# IV_FET_Array_v2.net
KiCad netlist of a schematic drawn in EAGLE
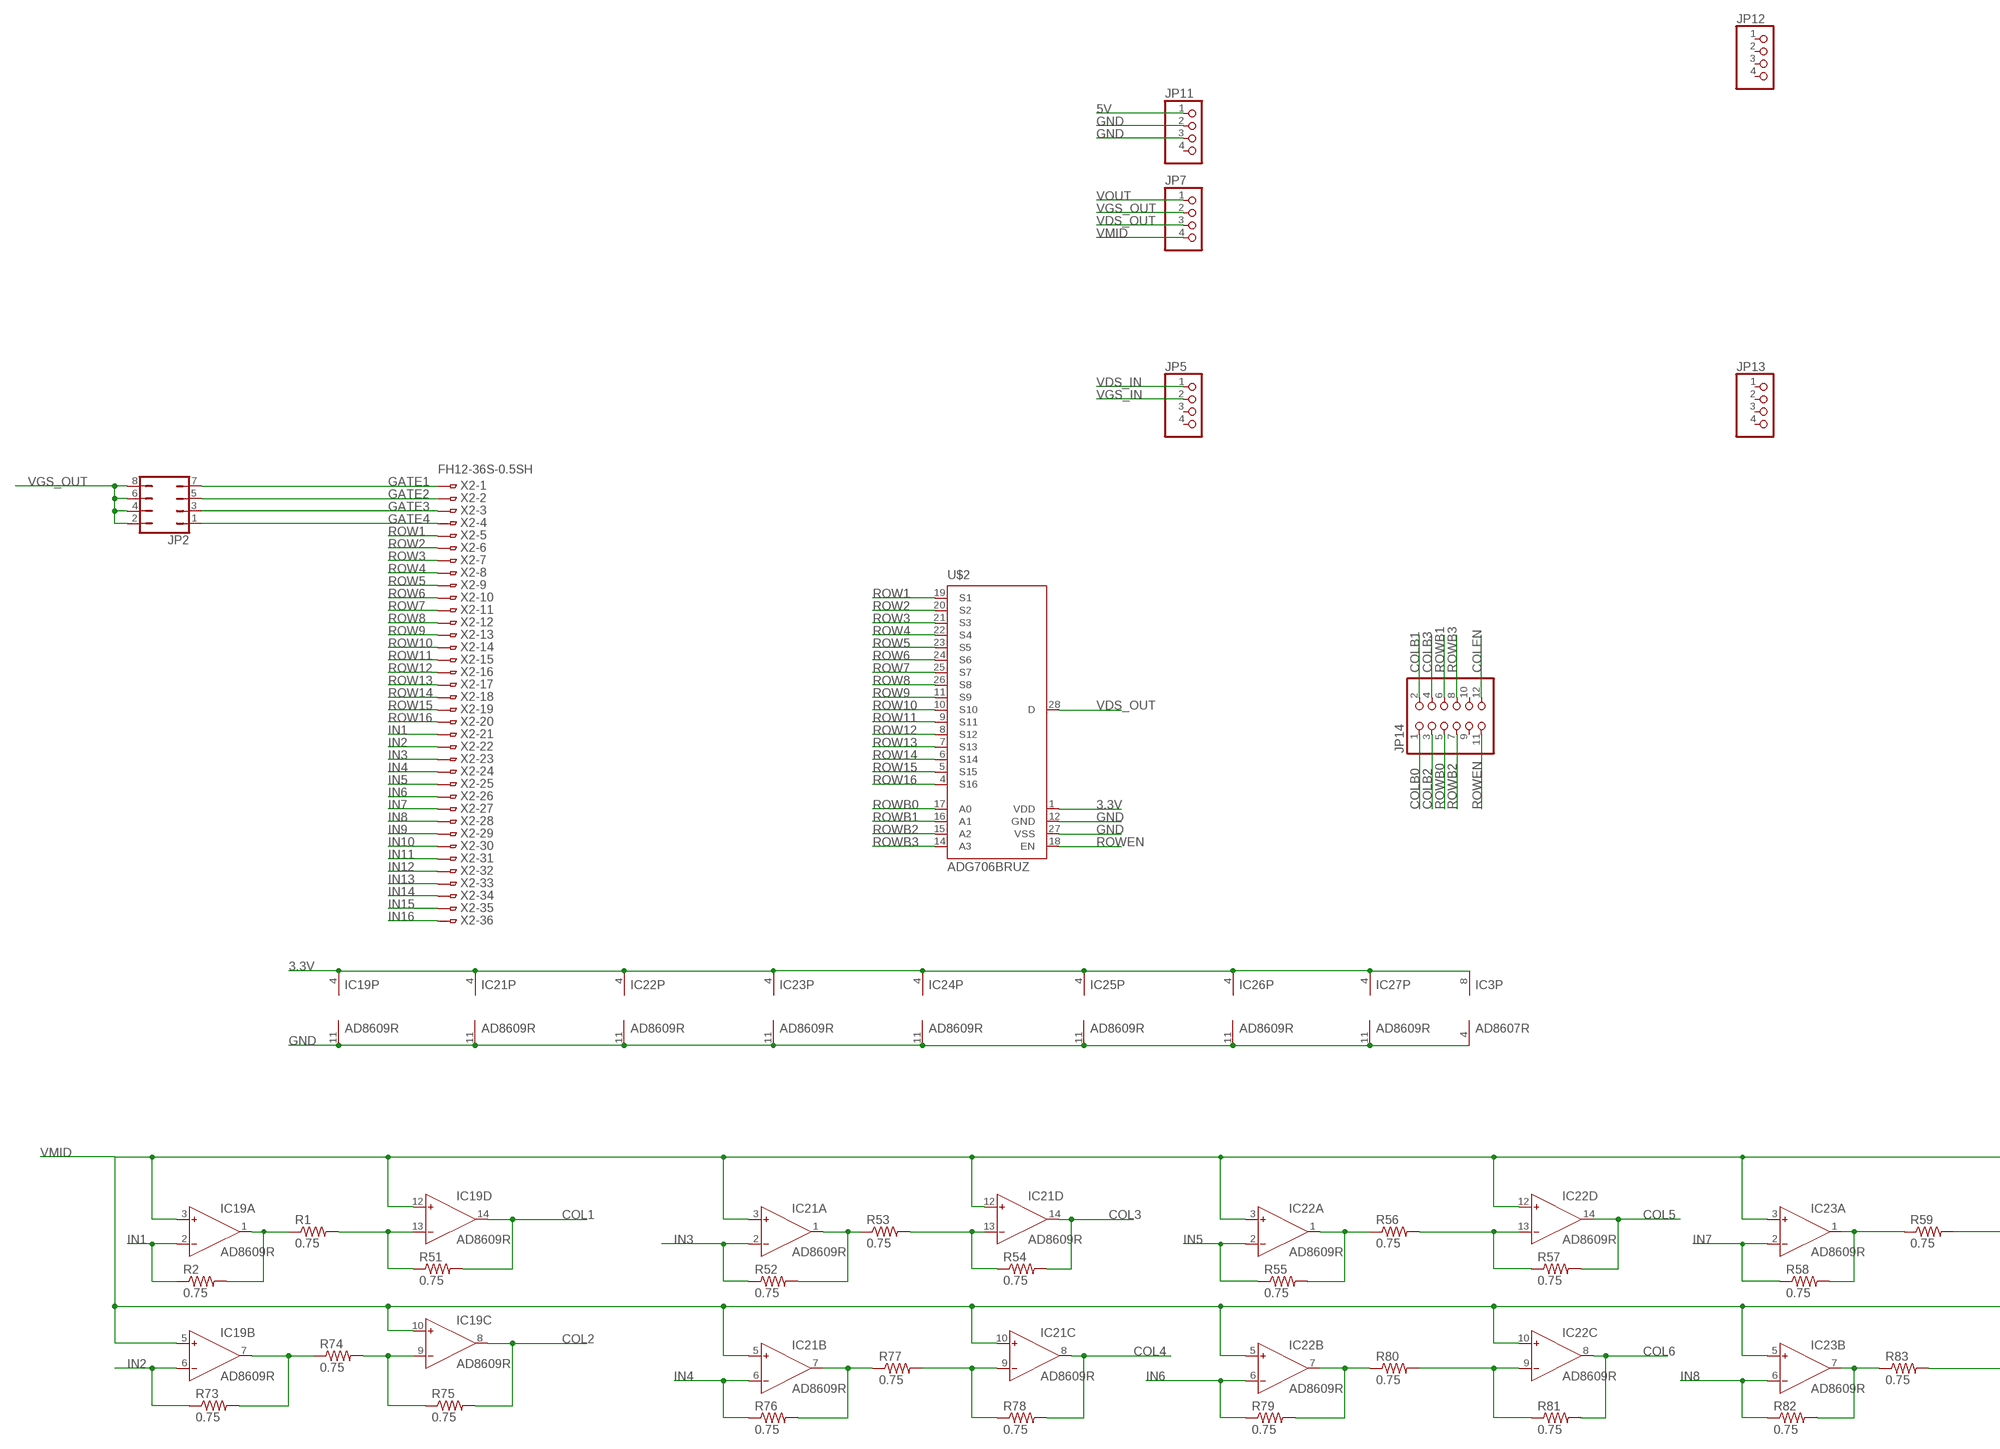
[diagram p0: schematic, sheet 1, part 1 of 2]
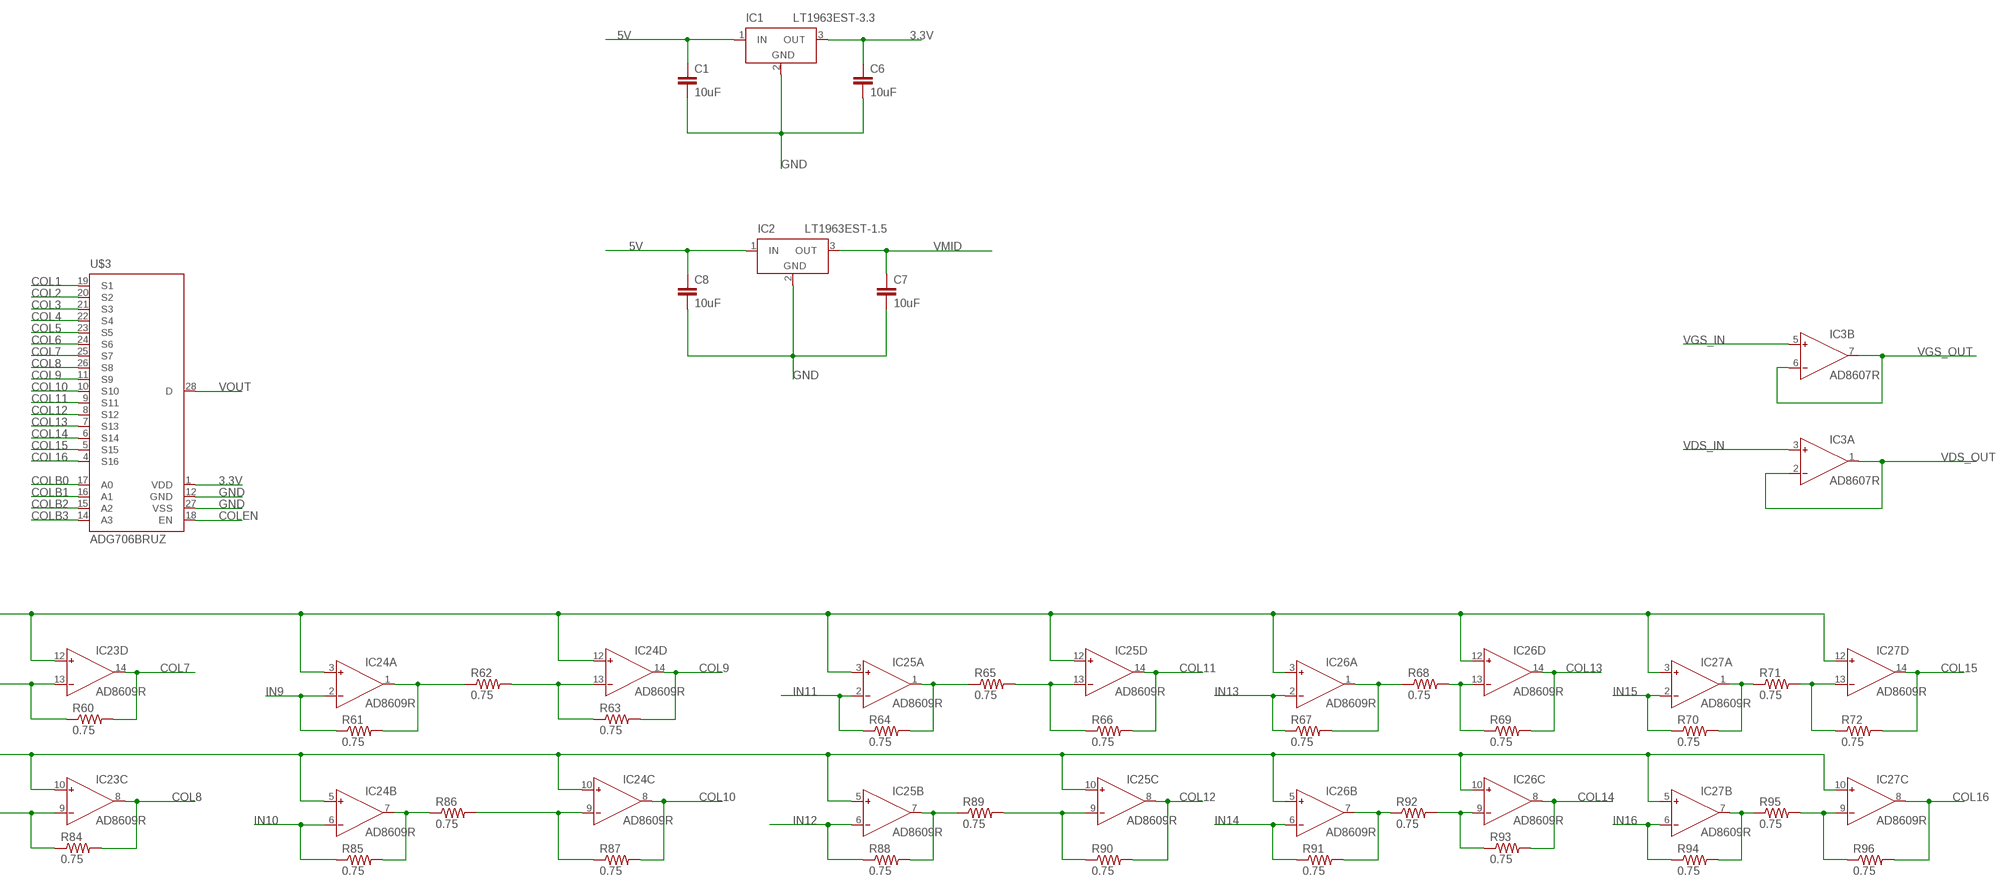
[diagram p1: schematic, sheet 1, part 2 of 2]

(export (version "E")
  (design (tool "Eeschema 10.0.6"))
  (components
    (comp (ref "C1")
      (value "10uF")
      (footprint "eagle-import:1210")
      (libsource (lib "eagle-import") (part "22UF-16V-20%-(1210)"))
    )
    (comp (ref "C6")
      (value "10uF")
      (footprint "eagle-import:1210")
      (libsource (lib "eagle-import") (part "22UF-16V-20%-(1210)"))
    )
    (comp (ref "C7")
      (value "10uF")
      (footprint "eagle-import:1210")
      (libsource (lib "eagle-import") (part "22UF-16V-20%-(1210)"))
    )
    (comp (ref "C8")
      (value "10uF")
      (footprint "eagle-import:1210")
      (libsource (lib "eagle-import") (part "22UF-16V-20%-(1210)"))
    )
    (comp (ref "IC1")
      (value "LT1963EST-3.3")
      (footprint "eagle-import:SOT223")
      (libsource (lib "eagle-import") (part "LT1963EST-3.3"))
    )
    (comp (ref "IC2")
      (value "LT1963EST-1.5")
      (footprint "eagle-import:SOT223")
      (libsource (lib "eagle-import") (part "LT1963EST-1.5"))
    )
    (comp (ref "IC3")
      (value "AD8607R")
      (footprint "eagle-import:SO8")
      (fields (field (name "MPN") "AD8607ARMZ-R2"))
      (libsource (lib "eagle-import") (part "AD8607R"))
    )
    (comp (ref "IC19")
      (value "AD8609R")
      (footprint "eagle-import:SO14")
      (fields (field (name "MPN") "AD8609ARZ"))
      (libsource (lib "eagle-import") (part "AD8609R"))
    )
    (comp (ref "IC21")
      (value "AD8609R")
      (footprint "eagle-import:SO14")
      (fields (field (name "MPN") "AD8609ARZ"))
      (libsource (lib "eagle-import") (part "AD8609R"))
    )
    (comp (ref "IC22")
      (value "AD8609R")
      (footprint "eagle-import:SO14")
      (fields (field (name "MPN") "AD8609ARZ"))
      (libsource (lib "eagle-import") (part "AD8609R"))
    )
    (comp (ref "IC23")
      (value "AD8609R")
      (footprint "eagle-import:SO14")
      (fields (field (name "MPN") "AD8609ARZ"))
      (libsource (lib "eagle-import") (part "AD8609R"))
    )
    (comp (ref "IC24")
      (value "AD8609R")
      (footprint "eagle-import:SO14")
      (fields (field (name "MPN") "AD8609ARZ"))
      (libsource (lib "eagle-import") (part "AD8609R"))
    )
    (comp (ref "IC25")
      (value "AD8609R")
      (footprint "eagle-import:SO14")
      (fields (field (name "MPN") "AD8609ARZ"))
      (libsource (lib "eagle-import") (part "AD8609R"))
    )
    (comp (ref "IC26")
      (value "AD8609R")
      (footprint "eagle-import:SO14")
      (fields (field (name "MPN") "AD8609ARZ"))
      (libsource (lib "eagle-import") (part "AD8609R"))
    )
    (comp (ref "IC27")
      (value "AD8609R")
      (footprint "eagle-import:SO14")
      (fields (field (name "MPN") "AD8609ARZ"))
      (libsource (lib "eagle-import") (part "AD8609R"))
    )
    (comp (ref "JP2")
      (value "JP4Q")
      (footprint "eagle-import:JP4Q")
      (libsource (lib "eagle-import") (part "JP4Q"))
    )
    (comp (ref "JP5")
      (value "PINHD-1X4")
      (footprint "eagle-import:1X04")
      (libsource (lib "eagle-import") (part "PINHD-1X4"))
    )
    (comp (ref "JP7")
      (value "PINHD-1X4")
      (footprint "eagle-import:1X04")
      (libsource (lib "eagle-import") (part "PINHD-1X4"))
    )
    (comp (ref "JP11")
      (value "PINHD-1X4")
      (footprint "eagle-import:1X04")
      (libsource (lib "eagle-import") (part "PINHD-1X4"))
    )
    (comp (ref "JP12")
      (value "PINHD-1X4")
      (footprint "eagle-import:1X04")
      (libsource (lib "eagle-import") (part "PINHD-1X4"))
    )
    (comp (ref "JP13")
      (value "PINHD-1X4")
      (footprint "eagle-import:1X04")
      (libsource (lib "eagle-import") (part "PINHD-1X4"))
    )
    (comp (ref "JP14")
      (value "PINHD-2X6")
      (footprint "eagle-import:2X06")
      (libsource (lib "eagle-import") (part "PINHD-2X6"))
    )
    (comp (ref "R1")
      (value "0.75")
      (footprint "eagle-import:0805")
      (libsource (lib "eagle-import") (part "0.75OHM-1/4W-1%(0805)"))
    )
    (comp (ref "R2")
      (value "0.75")
      (footprint "eagle-import:0805")
      (libsource (lib "eagle-import") (part "0.75OHM-1/4W-1%(0805)"))
    )
    (comp (ref "R51")
      (value "0.75")
      (footprint "eagle-import:0805")
      (libsource (lib "eagle-import") (part "0.75OHM-1/4W-1%(0805)"))
    )
    (comp (ref "R52")
      (value "0.75")
      (footprint "eagle-import:0805")
      (libsource (lib "eagle-import") (part "0.75OHM-1/4W-1%(0805)"))
    )
    (comp (ref "R53")
      (value "0.75")
      (footprint "eagle-import:0805")
      (libsource (lib "eagle-import") (part "0.75OHM-1/4W-1%(0805)"))
    )
    (comp (ref "R54")
      (value "0.75")
      (footprint "eagle-import:0805")
      (libsource (lib "eagle-import") (part "0.75OHM-1/4W-1%(0805)"))
    )
    (comp (ref "R55")
      (value "0.75")
      (footprint "eagle-import:0805")
      (libsource (lib "eagle-import") (part "0.75OHM-1/4W-1%(0805)"))
    )
    (comp (ref "R56")
      (value "0.75")
      (footprint "eagle-import:0805")
      (libsource (lib "eagle-import") (part "0.75OHM-1/4W-1%(0805)"))
    )
    (comp (ref "R57")
      (value "0.75")
      (footprint "eagle-import:0805")
      (libsource (lib "eagle-import") (part "0.75OHM-1/4W-1%(0805)"))
    )
    (comp (ref "R58")
      (value "0.75")
      (footprint "eagle-import:0805")
      (libsource (lib "eagle-import") (part "0.75OHM-1/4W-1%(0805)"))
    )
    (comp (ref "R59")
      (value "0.75")
      (footprint "eagle-import:0805")
      (libsource (lib "eagle-import") (part "0.75OHM-1/4W-1%(0805)"))
    )
    (comp (ref "R60")
      (value "0.75")
      (footprint "eagle-import:0805")
      (libsource (lib "eagle-import") (part "0.75OHM-1/4W-1%(0805)"))
    )
    (comp (ref "R61")
      (value "0.75")
      (footprint "eagle-import:0805")
      (libsource (lib "eagle-import") (part "0.75OHM-1/4W-1%(0805)"))
    )
    (comp (ref "R62")
      (value "0.75")
      (footprint "eagle-import:0805")
      (libsource (lib "eagle-import") (part "0.75OHM-1/4W-1%(0805)"))
    )
    (comp (ref "R63")
      (value "0.75")
      (footprint "eagle-import:0805")
      (libsource (lib "eagle-import") (part "0.75OHM-1/4W-1%(0805)"))
    )
    (comp (ref "R64")
      (value "0.75")
      (footprint "eagle-import:0805")
      (libsource (lib "eagle-import") (part "0.75OHM-1/4W-1%(0805)"))
    )
    (comp (ref "R65")
      (value "0.75")
      (footprint "eagle-import:0805")
      (libsource (lib "eagle-import") (part "0.75OHM-1/4W-1%(0805)"))
    )
    (comp (ref "R66")
      (value "0.75")
      (footprint "eagle-import:0805")
      (libsource (lib "eagle-import") (part "0.75OHM-1/4W-1%(0805)"))
    )
    (comp (ref "R67")
      (value "0.75")
      (footprint "eagle-import:0805")
      (libsource (lib "eagle-import") (part "0.75OHM-1/4W-1%(0805)"))
    )
    (comp (ref "R68")
      (value "0.75")
      (footprint "eagle-import:0805")
      (libsource (lib "eagle-import") (part "0.75OHM-1/4W-1%(0805)"))
    )
    (comp (ref "R69")
      (value "0.75")
      (footprint "eagle-import:0805")
      (libsource (lib "eagle-import") (part "0.75OHM-1/4W-1%(0805)"))
    )
    (comp (ref "R70")
      (value "0.75")
      (footprint "eagle-import:0805")
      (libsource (lib "eagle-import") (part "0.75OHM-1/4W-1%(0805)"))
    )
    (comp (ref "R71")
      (value "0.75")
      (footprint "eagle-import:0805")
      (libsource (lib "eagle-import") (part "0.75OHM-1/4W-1%(0805)"))
    )
    (comp (ref "R72")
      (value "0.75")
      (footprint "eagle-import:0805")
      (libsource (lib "eagle-import") (part "0.75OHM-1/4W-1%(0805)"))
    )
    (comp (ref "R73")
      (value "0.75")
      (footprint "eagle-import:0805")
      (libsource (lib "eagle-import") (part "0.75OHM-1/4W-1%(0805)"))
    )
    (comp (ref "R74")
      (value "0.75")
      (footprint "eagle-import:0805")
      (libsource (lib "eagle-import") (part "0.75OHM-1/4W-1%(0805)"))
    )
    (comp (ref "R75")
      (value "0.75")
      (footprint "eagle-import:0805")
      (libsource (lib "eagle-import") (part "0.75OHM-1/4W-1%(0805)"))
    )
    (comp (ref "R76")
      (value "0.75")
      (footprint "eagle-import:0805")
      (libsource (lib "eagle-import") (part "0.75OHM-1/4W-1%(0805)"))
    )
    (comp (ref "R77")
      (value "0.75")
      (footprint "eagle-import:0805")
      (libsource (lib "eagle-import") (part "0.75OHM-1/4W-1%(0805)"))
    )
    (comp (ref "R78")
      (value "0.75")
      (footprint "eagle-import:0805")
      (libsource (lib "eagle-import") (part "0.75OHM-1/4W-1%(0805)"))
    )
    (comp (ref "R79")
      (value "0.75")
      (footprint "eagle-import:0805")
      (libsource (lib "eagle-import") (part "0.75OHM-1/4W-1%(0805)"))
    )
    (comp (ref "R80")
      (value "0.75")
      (footprint "eagle-import:0805")
      (libsource (lib "eagle-import") (part "0.75OHM-1/4W-1%(0805)"))
    )
    (comp (ref "R81")
      (value "0.75")
      (footprint "eagle-import:0805")
      (libsource (lib "eagle-import") (part "0.75OHM-1/4W-1%(0805)"))
    )
    (comp (ref "R82")
      (value "0.75")
      (footprint "eagle-import:0805")
      (libsource (lib "eagle-import") (part "0.75OHM-1/4W-1%(0805)"))
    )
    (comp (ref "R83")
      (value "0.75")
      (footprint "eagle-import:0805")
      (libsource (lib "eagle-import") (part "0.75OHM-1/4W-1%(0805)"))
    )
    (comp (ref "R84")
      (value "0.75")
      (footprint "eagle-import:0805")
      (libsource (lib "eagle-import") (part "0.75OHM-1/4W-1%(0805)"))
    )
    (comp (ref "R85")
      (value "0.75")
      (footprint "eagle-import:0805")
      (libsource (lib "eagle-import") (part "0.75OHM-1/4W-1%(0805)"))
    )
    (comp (ref "R86")
      (value "0.75")
      (footprint "eagle-import:0805")
      (libsource (lib "eagle-import") (part "0.75OHM-1/4W-1%(0805)"))
    )
    (comp (ref "R87")
      (value "0.75")
      (footprint "eagle-import:0805")
      (libsource (lib "eagle-import") (part "0.75OHM-1/4W-1%(0805)"))
    )
    (comp (ref "R88")
      (value "0.75")
      (footprint "eagle-import:0805")
      (libsource (lib "eagle-import") (part "0.75OHM-1/4W-1%(0805)"))
    )
    (comp (ref "R89")
      (value "0.75")
      (footprint "eagle-import:0805")
      (libsource (lib "eagle-import") (part "0.75OHM-1/4W-1%(0805)"))
    )
    (comp (ref "R90")
      (value "0.75")
      (footprint "eagle-import:0805")
      (libsource (lib "eagle-import") (part "0.75OHM-1/4W-1%(0805)"))
    )
    (comp (ref "R91")
      (value "0.75")
      (footprint "eagle-import:0805")
      (libsource (lib "eagle-import") (part "0.75OHM-1/4W-1%(0805)"))
    )
    (comp (ref "R92")
      (value "0.75")
      (footprint "eagle-import:0805")
      (libsource (lib "eagle-import") (part "0.75OHM-1/4W-1%(0805)"))
    )
    (comp (ref "R93")
      (value "0.75")
      (footprint "eagle-import:0805")
      (libsource (lib "eagle-import") (part "0.75OHM-1/4W-1%(0805)"))
    )
    (comp (ref "R94")
      (value "0.75")
      (footprint "eagle-import:0805")
      (libsource (lib "eagle-import") (part "0.75OHM-1/4W-1%(0805)"))
    )
    (comp (ref "R95")
      (value "0.75")
      (footprint "eagle-import:0805")
      (libsource (lib "eagle-import") (part "0.75OHM-1/4W-1%(0805)"))
    )
    (comp (ref "R96")
      (value "0.75")
      (footprint "eagle-import:0805")
      (libsource (lib "eagle-import") (part "0.75OHM-1/4W-1%(0805)"))
    )
    (comp (ref "U$2")
      (value "ADG706BRUZ")
      (footprint "eagle-import:TSSOP28")
      (libsource (lib "eagle-import") (part "ADG706BRUZ"))
    )
    (comp (ref "U$3")
      (value "ADG706BRUZ")
      (footprint "eagle-import:TSSOP28")
      (libsource (lib "eagle-import") (part "ADG706BRUZ"))
    )
    (comp (ref "X2")
      (value "FH12-36S-0.5SH")
      (footprint "eagle-import:FH12-36S-0.5SH")
      (libsource (lib "eagle-import") (part "FH12-36S-0.5SH"))
    )
  )
  (nets
    (net (code "1") (name "/3.3V") (class "Default")
      (node (ref "C6") (pin "1") (pinfunction "1_1") (pintype "passive"))
      (node (ref "IC1") (pin "3") (pinfunction "OUT_3") (pintype "output"))
      (node (ref "IC19") (pin "4") (pinfunction "V+_4") (pintype "power_in"))
      (node (ref "IC21") (pin "4") (pinfunction "V+_4") (pintype "power_in"))
      (node (ref "IC22") (pin "4") (pinfunction "V+_4") (pintype "power_in"))
      (node (ref "IC23") (pin "4") (pinfunction "V+_4") (pintype "power_in"))
      (node (ref "IC24") (pin "4") (pinfunction "V+_4") (pintype "power_in"))
      (node (ref "IC25") (pin "4") (pinfunction "V+_4") (pintype "power_in"))
      (node (ref "IC26") (pin "4") (pinfunction "V+_4") (pintype "power_in"))
      (node (ref "IC27") (pin "4") (pinfunction "V+_4") (pintype "power_in"))
      (node (ref "IC3") (pin "8") (pinfunction "V+_8") (pintype "power_in"))
      (node (ref "U$2") (pin "1") (pinfunction "VDD_1") (pintype "power_in"))
      (node (ref "U$3") (pin "1") (pinfunction "VDD_1") (pintype "power_in"))
    )
    (net (code "2") (name "/5V") (class "Default")
      (node (ref "C1") (pin "1") (pinfunction "1_1") (pintype "passive"))
      (node (ref "C8") (pin "1") (pinfunction "1_1") (pintype "passive"))
      (node (ref "IC1") (pin "1") (pinfunction "IN_1") (pintype "input"))
      (node (ref "IC2") (pin "1") (pinfunction "IN_1") (pintype "input"))
      (node (ref "JP11") (pin "1") (pinfunction "1_1") (pintype "passive"))
    )
    (net (code "3") (name "/COL1") (class "Default")
      (node (ref "IC19") (pin "14") (pinfunction "OUT_14") (pintype "output"))
      (node (ref "R51") (pin "2") (pinfunction "2_2") (pintype "passive"))
      (node (ref "U$3") (pin "19") (pinfunction "S1_19") (pintype "bidirectional"))
    )
    (net (code "4") (name "/COL2") (class "Default")
      (node (ref "IC19") (pin "8") (pinfunction "OUT_8") (pintype "output"))
      (node (ref "R75") (pin "2") (pinfunction "2_2") (pintype "passive"))
      (node (ref "U$3") (pin "20") (pinfunction "S2_20") (pintype "bidirectional"))
    )
    (net (code "5") (name "/COL3") (class "Default")
      (node (ref "IC21") (pin "14") (pinfunction "OUT_14") (pintype "output"))
      (node (ref "R54") (pin "2") (pinfunction "2_2") (pintype "passive"))
      (node (ref "U$3") (pin "21") (pinfunction "S3_21") (pintype "bidirectional"))
    )
    (net (code "6") (name "/COL4") (class "Default")
      (node (ref "IC21") (pin "8") (pinfunction "OUT_8") (pintype "output"))
      (node (ref "R78") (pin "2") (pinfunction "2_2") (pintype "passive"))
      (node (ref "U$3") (pin "22") (pinfunction "S4_22") (pintype "bidirectional"))
    )
    (net (code "7") (name "/COL5") (class "Default")
      (node (ref "IC22") (pin "14") (pinfunction "OUT_14") (pintype "output"))
      (node (ref "R57") (pin "2") (pinfunction "2_2") (pintype "passive"))
      (node (ref "U$3") (pin "23") (pinfunction "S5_23") (pintype "bidirectional"))
    )
    (net (code "8") (name "/COL6") (class "Default")
      (node (ref "IC22") (pin "8") (pinfunction "OUT_8") (pintype "output"))
      (node (ref "R81") (pin "2") (pinfunction "2_2") (pintype "passive"))
      (node (ref "U$3") (pin "24") (pinfunction "S6_24") (pintype "bidirectional"))
    )
    (net (code "9") (name "/COL7") (class "Default")
      (node (ref "IC23") (pin "14") (pinfunction "OUT_14") (pintype "output"))
      (node (ref "R60") (pin "2") (pinfunction "2_2") (pintype "passive"))
      (node (ref "U$3") (pin "25") (pinfunction "S7_25") (pintype "bidirectional"))
    )
    (net (code "10") (name "/COL8") (class "Default")
      (node (ref "IC23") (pin "8") (pinfunction "OUT_8") (pintype "output"))
      (node (ref "R84") (pin "2") (pinfunction "2_2") (pintype "passive"))
      (node (ref "U$3") (pin "26") (pinfunction "S8_26") (pintype "bidirectional"))
    )
    (net (code "11") (name "/COL9") (class "Default")
      (node (ref "IC24") (pin "14") (pinfunction "OUT_14") (pintype "output"))
      (node (ref "R63") (pin "2") (pinfunction "2_2") (pintype "passive"))
      (node (ref "U$3") (pin "11") (pinfunction "S9_11") (pintype "bidirectional"))
    )
    (net (code "12") (name "/COL10") (class "Default")
      (node (ref "IC24") (pin "8") (pinfunction "OUT_8") (pintype "output"))
      (node (ref "R87") (pin "2") (pinfunction "2_2") (pintype "passive"))
      (node (ref "U$3") (pin "10") (pinfunction "S10_10") (pintype "bidirectional"))
    )
    (net (code "13") (name "/COL11") (class "Default")
      (node (ref "IC25") (pin "14") (pinfunction "OUT_14") (pintype "output"))
      (node (ref "R66") (pin "2") (pinfunction "2_2") (pintype "passive"))
      (node (ref "U$3") (pin "9") (pinfunction "S11_9") (pintype "bidirectional"))
    )
    (net (code "14") (name "/COL12") (class "Default")
      (node (ref "IC25") (pin "8") (pinfunction "OUT_8") (pintype "output"))
      (node (ref "R90") (pin "2") (pinfunction "2_2") (pintype "passive"))
      (node (ref "U$3") (pin "8") (pinfunction "S12_8") (pintype "bidirectional"))
    )
    (net (code "15") (name "/COL13") (class "Default")
      (node (ref "IC26") (pin "14") (pinfunction "OUT_14") (pintype "output"))
      (node (ref "R69") (pin "2") (pinfunction "2_2") (pintype "passive"))
      (node (ref "U$3") (pin "7") (pinfunction "S13_7") (pintype "bidirectional"))
    )
    (net (code "16") (name "/COL14") (class "Default")
      (node (ref "IC26") (pin "8") (pinfunction "OUT_8") (pintype "output"))
      (node (ref "R93") (pin "2") (pinfunction "2_2") (pintype "passive"))
      (node (ref "U$3") (pin "6") (pinfunction "S14_6") (pintype "bidirectional"))
    )
    (net (code "17") (name "/COL15") (class "Default")
      (node (ref "IC27") (pin "14") (pinfunction "OUT_14") (pintype "output"))
      (node (ref "R72") (pin "2") (pinfunction "2_2") (pintype "passive"))
      (node (ref "U$3") (pin "5") (pinfunction "S15_5") (pintype "bidirectional"))
    )
    (net (code "18") (name "/COL16") (class "Default")
      (node (ref "IC27") (pin "8") (pinfunction "OUT_8") (pintype "output"))
      (node (ref "R96") (pin "2") (pinfunction "2_2") (pintype "passive"))
      (node (ref "U$3") (pin "4") (pinfunction "S16_4") (pintype "bidirectional"))
    )
    (net (code "19") (name "/COLB0") (class "Default")
      (node (ref "JP14") (pin "1") (pinfunction "1_1") (pintype "passive"))
      (node (ref "U$3") (pin "17") (pinfunction "A0_17") (pintype "input"))
    )
    (net (code "20") (name "/COLB1") (class "Default")
      (node (ref "JP14") (pin "2") (pinfunction "2_2") (pintype "passive"))
      (node (ref "U$3") (pin "16") (pinfunction "A1_16") (pintype "input"))
    )
    (net (code "21") (name "/COLB2") (class "Default")
      (node (ref "JP14") (pin "3") (pinfunction "3_3") (pintype "passive"))
      (node (ref "U$3") (pin "15") (pinfunction "A2_15") (pintype "input"))
    )
    (net (code "22") (name "/COLB3") (class "Default")
      (node (ref "JP14") (pin "4") (pinfunction "4_4") (pintype "passive"))
      (node (ref "U$3") (pin "14") (pinfunction "A3_14") (pintype "input"))
    )
    (net (code "23") (name "/COLEN") (class "Default")
      (node (ref "JP14") (pin "12") (pinfunction "12_12") (pintype "passive"))
      (node (ref "U$3") (pin "18") (pinfunction "EN_18") (pintype "input"))
    )
    (net (code "24") (name "/GATE1") (class "Default")
      (node (ref "JP2") (pin "7") (pinfunction "7_7") (pintype "passive"))
      (node (ref "X2") (pin "1") (pinfunction "1_1") (pintype "passive"))
    )
    (net (code "25") (name "/GATE2") (class "Default")
      (node (ref "JP2") (pin "5") (pinfunction "5_5") (pintype "passive"))
      (node (ref "X2") (pin "2") (pinfunction "1_2") (pintype "passive"))
    )
    (net (code "26") (name "/GATE3") (class "Default")
      (node (ref "JP2") (pin "3") (pinfunction "3_3") (pintype "passive"))
      (node (ref "X2") (pin "3") (pinfunction "1_3") (pintype "passive"))
    )
    (net (code "27") (name "/GATE4") (class "Default")
      (node (ref "JP2") (pin "1") (pinfunction "1_1") (pintype "passive"))
      (node (ref "X2") (pin "4") (pinfunction "1_4") (pintype "passive"))
    )
    (net (code "28") (name "/GND") (class "Default")
      (node (ref "C1") (pin "2") (pinfunction "2_2") (pintype "passive"))
      (node (ref "C6") (pin "2") (pinfunction "2_2") (pintype "passive"))
      (node (ref "C7") (pin "2") (pinfunction "2_2") (pintype "passive"))
      (node (ref "C8") (pin "2") (pinfunction "2_2") (pintype "passive"))
      (node (ref "IC1") (pin "2") (pinfunction "GND_2") (pintype "power_in"))
      (node (ref "IC19") (pin "11") (pinfunction "V-_11") (pintype "power_in"))
      (node (ref "IC2") (pin "2") (pinfunction "GND_2") (pintype "power_in"))
      (node (ref "IC21") (pin "11") (pinfunction "V-_11") (pintype "power_in"))
      (node (ref "IC22") (pin "11") (pinfunction "V-_11") (pintype "power_in"))
      (node (ref "IC23") (pin "11") (pinfunction "V-_11") (pintype "power_in"))
      (node (ref "IC24") (pin "11") (pinfunction "V-_11") (pintype "power_in"))
      (node (ref "IC25") (pin "11") (pinfunction "V-_11") (pintype "power_in"))
      (node (ref "IC26") (pin "11") (pinfunction "V-_11") (pintype "power_in"))
      (node (ref "IC27") (pin "11") (pinfunction "V-_11") (pintype "power_in"))
      (node (ref "IC3") (pin "4") (pinfunction "V-_4") (pintype "power_in"))
      (node (ref "JP11") (pin "2") (pinfunction "2_2") (pintype "passive"))
      (node (ref "JP11") (pin "3") (pinfunction "3_3") (pintype "passive"))
      (node (ref "U$2") (pin "12") (pinfunction "GND_12") (pintype "power_in"))
      (node (ref "U$2") (pin "27") (pinfunction "VSS_27") (pintype "power_in"))
      (node (ref "U$3") (pin "12") (pinfunction "GND_12") (pintype "power_in"))
      (node (ref "U$3") (pin "27") (pinfunction "VSS_27") (pintype "power_in"))
    )
    (net (code "29") (name "/IN1") (class "Default")
      (node (ref "IC19") (pin "2") (pinfunction "IN-_2") (pintype "input"))
      (node (ref "R2") (pin "1") (pinfunction "1_1") (pintype "passive"))
      (node (ref "X2") (pin "21") (pinfunction "1_21") (pintype "passive"))
    )
    (net (code "30") (name "/IN2") (class "Default")
      (node (ref "IC19") (pin "6") (pinfunction "IN-_6") (pintype "input"))
      (node (ref "R73") (pin "1") (pinfunction "1_1") (pintype "passive"))
      (node (ref "X2") (pin "22") (pinfunction "1_22") (pintype "passive"))
    )
    (net (code "31") (name "/IN3") (class "Default")
      (node (ref "IC21") (pin "2") (pinfunction "IN-_2") (pintype "input"))
      (node (ref "R52") (pin "1") (pinfunction "1_1") (pintype "passive"))
      (node (ref "X2") (pin "23") (pinfunction "1_23") (pintype "passive"))
    )
    (net (code "32") (name "/IN4") (class "Default")
      (node (ref "IC21") (pin "6") (pinfunction "IN-_6") (pintype "input"))
      (node (ref "R76") (pin "1") (pinfunction "1_1") (pintype "passive"))
      (node (ref "X2") (pin "24") (pinfunction "1_24") (pintype "passive"))
    )
    (net (code "33") (name "/IN5") (class "Default")
      (node (ref "IC22") (pin "2") (pinfunction "IN-_2") (pintype "input"))
      (node (ref "R55") (pin "1") (pinfunction "1_1") (pintype "passive"))
      (node (ref "X2") (pin "25") (pinfunction "1_25") (pintype "passive"))
    )
    (net (code "34") (name "/IN6") (class "Default")
      (node (ref "IC22") (pin "6") (pinfunction "IN-_6") (pintype "input"))
      (node (ref "R79") (pin "1") (pinfunction "1_1") (pintype "passive"))
      (node (ref "X2") (pin "26") (pinfunction "1_26") (pintype "passive"))
    )
    (net (code "35") (name "/IN7") (class "Default")
      (node (ref "IC23") (pin "2") (pinfunction "IN-_2") (pintype "input"))
      (node (ref "R58") (pin "1") (pinfunction "1_1") (pintype "passive"))
      (node (ref "X2") (pin "27") (pinfunction "1_27") (pintype "passive"))
    )
    (net (code "36") (name "/IN8") (class "Default")
      (node (ref "IC23") (pin "6") (pinfunction "IN-_6") (pintype "input"))
      (node (ref "R82") (pin "1") (pinfunction "1_1") (pintype "passive"))
      (node (ref "X2") (pin "28") (pinfunction "1_28") (pintype "passive"))
    )
    (net (code "37") (name "/IN9") (class "Default")
      (node (ref "IC24") (pin "2") (pinfunction "IN-_2") (pintype "input"))
      (node (ref "R61") (pin "1") (pinfunction "1_1") (pintype "passive"))
      (node (ref "X2") (pin "29") (pinfunction "1_29") (pintype "passive"))
    )
    (net (code "38") (name "/IN10") (class "Default")
      (node (ref "IC24") (pin "6") (pinfunction "IN-_6") (pintype "input"))
      (node (ref "R85") (pin "1") (pinfunction "1_1") (pintype "passive"))
      (node (ref "X2") (pin "30") (pinfunction "1_30") (pintype "passive"))
    )
    (net (code "39") (name "/IN11") (class "Default")
      (node (ref "IC25") (pin "2") (pinfunction "IN-_2") (pintype "input"))
      (node (ref "R64") (pin "1") (pinfunction "1_1") (pintype "passive"))
      (node (ref "X2") (pin "31") (pinfunction "1_31") (pintype "passive"))
    )
    (net (code "40") (name "/IN12") (class "Default")
      (node (ref "IC25") (pin "6") (pinfunction "IN-_6") (pintype "input"))
      (node (ref "R88") (pin "1") (pinfunction "1_1") (pintype "passive"))
      (node (ref "X2") (pin "32") (pinfunction "1_32") (pintype "passive"))
    )
    (net (code "41") (name "/IN13") (class "Default")
      (node (ref "IC26") (pin "2") (pinfunction "IN-_2") (pintype "input"))
      (node (ref "R67") (pin "1") (pinfunction "1_1") (pintype "passive"))
      (node (ref "X2") (pin "33") (pinfunction "1_33") (pintype "passive"))
    )
    (net (code "42") (name "/IN14") (class "Default")
      (node (ref "IC26") (pin "6") (pinfunction "IN-_6") (pintype "input"))
      (node (ref "R91") (pin "1") (pinfunction "1_1") (pintype "passive"))
      (node (ref "X2") (pin "34") (pinfunction "1_34") (pintype "passive"))
    )
    (net (code "43") (name "/IN15") (class "Default")
      (node (ref "IC27") (pin "2") (pinfunction "IN-_2") (pintype "input"))
      (node (ref "R70") (pin "1") (pinfunction "1_1") (pintype "passive"))
      (node (ref "X2") (pin "35") (pinfunction "1_35") (pintype "passive"))
    )
    (net (code "44") (name "/IN16") (class "Default")
      (node (ref "IC27") (pin "6") (pinfunction "IN-_6") (pintype "input"))
      (node (ref "R94") (pin "1") (pinfunction "1_1") (pintype "passive"))
      (node (ref "X2") (pin "36") (pinfunction "1_36") (pintype "passive"))
    )
    (net (code "45") (name "/ROW1") (class "Default")
      (node (ref "U$2") (pin "19") (pinfunction "S1_19") (pintype "bidirectional"))
      (node (ref "X2") (pin "5") (pinfunction "1_5") (pintype "passive"))
    )
    (net (code "46") (name "/ROW2") (class "Default")
      (node (ref "U$2") (pin "20") (pinfunction "S2_20") (pintype "bidirectional"))
      (node (ref "X2") (pin "6") (pinfunction "1_6") (pintype "passive"))
    )
    (net (code "47") (name "/ROW3") (class "Default")
      (node (ref "U$2") (pin "21") (pinfunction "S3_21") (pintype "bidirectional"))
      (node (ref "X2") (pin "7") (pinfunction "1_7") (pintype "passive"))
    )
    (net (code "48") (name "/ROW4") (class "Default")
      (node (ref "U$2") (pin "22") (pinfunction "S4_22") (pintype "bidirectional"))
      (node (ref "X2") (pin "8") (pinfunction "1_8") (pintype "passive"))
    )
    (net (code "49") (name "/ROW5") (class "Default")
      (node (ref "U$2") (pin "23") (pinfunction "S5_23") (pintype "bidirectional"))
      (node (ref "X2") (pin "9") (pinfunction "1_9") (pintype "passive"))
    )
    (net (code "50") (name "/ROW6") (class "Default")
      (node (ref "U$2") (pin "24") (pinfunction "S6_24") (pintype "bidirectional"))
      (node (ref "X2") (pin "10") (pinfunction "1_10") (pintype "passive"))
    )
    (net (code "51") (name "/ROW7") (class "Default")
      (node (ref "U$2") (pin "25") (pinfunction "S7_25") (pintype "bidirectional"))
      (node (ref "X2") (pin "11") (pinfunction "1_11") (pintype "passive"))
    )
    (net (code "52") (name "/ROW8") (class "Default")
      (node (ref "U$2") (pin "26") (pinfunction "S8_26") (pintype "bidirectional"))
      (node (ref "X2") (pin "12") (pinfunction "1_12") (pintype "passive"))
    )
    (net (code "53") (name "/ROW9") (class "Default")
      (node (ref "U$2") (pin "11") (pinfunction "S9_11") (pintype "bidirectional"))
      (node (ref "X2") (pin "13") (pinfunction "1_13") (pintype "passive"))
    )
    (net (code "54") (name "/ROW10") (class "Default")
      (node (ref "U$2") (pin "10") (pinfunction "S10_10") (pintype "bidirectional"))
      (node (ref "X2") (pin "14") (pinfunction "1_14") (pintype "passive"))
    )
    (net (code "55") (name "/ROW11") (class "Default")
      (node (ref "U$2") (pin "9") (pinfunction "S11_9") (pintype "bidirectional"))
      (node (ref "X2") (pin "15") (pinfunction "1_15") (pintype "passive"))
    )
    (net (code "56") (name "/ROW12") (class "Default")
      (node (ref "U$2") (pin "8") (pinfunction "S12_8") (pintype "bidirectional"))
      (node (ref "X2") (pin "16") (pinfunction "1_16") (pintype "passive"))
    )
    (net (code "57") (name "/ROW13") (class "Default")
      (node (ref "U$2") (pin "7") (pinfunction "S13_7") (pintype "bidirectional"))
      (node (ref "X2") (pin "17") (pinfunction "1_17") (pintype "passive"))
    )
    (net (code "58") (name "/ROW14") (class "Default")
      (node (ref "U$2") (pin "6") (pinfunction "S14_6") (pintype "bidirectional"))
      (node (ref "X2") (pin "18") (pinfunction "1_18") (pintype "passive"))
    )
    (net (code "59") (name "/ROW15") (class "Default")
      (node (ref "U$2") (pin "5") (pinfunction "S15_5") (pintype "bidirectional"))
      (node (ref "X2") (pin "19") (pinfunction "1_19") (pintype "passive"))
    )
    (net (code "60") (name "/ROW16") (class "Default")
      (node (ref "U$2") (pin "4") (pinfunction "S16_4") (pintype "bidirectional"))
      (node (ref "X2") (pin "20") (pinfunction "1_20") (pintype "passive"))
    )
    (net (code "61") (name "/ROWB0") (class "Default")
      (node (ref "JP14") (pin "5") (pinfunction "5_5") (pintype "passive"))
      (node (ref "U$2") (pin "17") (pinfunction "A0_17") (pintype "input"))
    )
    (net (code "62") (name "/ROWB1") (class "Default")
      (node (ref "JP14") (pin "6") (pinfunction "6_6") (pintype "passive"))
      (node (ref "U$2") (pin "16") (pinfunction "A1_16") (pintype "input"))
    )
    (net (code "63") (name "/ROWB2") (class "Default")
      (node (ref "JP14") (pin "7") (pinfunction "7_7") (pintype "passive"))
      (node (ref "U$2") (pin "15") (pinfunction "A2_15") (pintype "input"))
    )
    (net (code "64") (name "/ROWB3") (class "Default")
      (node (ref "JP14") (pin "8") (pinfunction "8_8") (pintype "passive"))
      (node (ref "U$2") (pin "14") (pinfunction "A3_14") (pintype "input"))
    )
    (net (code "65") (name "/ROWEN") (class "Default")
      (node (ref "JP14") (pin "11") (pinfunction "11_11") (pintype "passive"))
      (node (ref "U$2") (pin "18") (pinfunction "EN_18") (pintype "input"))
    )
    (net (code "66") (name "/VDS_IN") (class "Default")
      (node (ref "IC3") (pin "3") (pinfunction "IN+_3") (pintype "input"))
      (node (ref "JP5") (pin "1") (pinfunction "1_1") (pintype "passive"))
    )
    (net (code "67") (name "/VDS_OUT") (class "Default")
      (node (ref "IC3") (pin "1") (pinfunction "OUT_1") (pintype "output"))
      (node (ref "IC3") (pin "2") (pinfunction "IN-_2") (pintype "input"))
      (node (ref "JP7") (pin "3") (pinfunction "3_3") (pintype "passive"))
      (node (ref "U$2") (pin "28") (pinfunction "D_28") (pintype "bidirectional"))
    )
    (net (code "68") (name "/VGS_IN") (class "Default")
      (node (ref "IC3") (pin "5") (pinfunction "IN+_5") (pintype "input"))
      (node (ref "JP5") (pin "2") (pinfunction "2_2") (pintype "passive"))
    )
    (net (code "69") (name "/VGS_OUT") (class "Default")
      (node (ref "IC3") (pin "6") (pinfunction "IN-_6") (pintype "input"))
      (node (ref "IC3") (pin "7") (pinfunction "OUT_7") (pintype "output"))
      (node (ref "JP2") (pin "2") (pinfunction "2_2") (pintype "passive"))
      (node (ref "JP2") (pin "4") (pinfunction "4_4") (pintype "passive"))
      (node (ref "JP2") (pin "6") (pinfunction "6_6") (pintype "passive"))
      (node (ref "JP2") (pin "8") (pinfunction "8_8") (pintype "passive"))
      (node (ref "JP7") (pin "2") (pinfunction "2_2") (pintype "passive"))
    )
    (net (code "70") (name "/VMID") (class "Default")
      (node (ref "C7") (pin "1") (pinfunction "1_1") (pintype "passive"))
      (node (ref "IC19") (pin "10") (pinfunction "IN+_10") (pintype "input"))
      (node (ref "IC19") (pin "12") (pinfunction "IN+_12") (pintype "input"))
      (node (ref "IC19") (pin "3") (pinfunction "IN+_3") (pintype "input"))
      (node (ref "IC19") (pin "5") (pinfunction "IN+_5") (pintype "input"))
      (node (ref "IC2") (pin "3") (pinfunction "OUT_3") (pintype "output"))
      (node (ref "IC21") (pin "10") (pinfunction "IN+_10") (pintype "input"))
      (node (ref "IC21") (pin "12") (pinfunction "IN+_12") (pintype "input"))
      (node (ref "IC21") (pin "3") (pinfunction "IN+_3") (pintype "input"))
      (node (ref "IC21") (pin "5") (pinfunction "IN+_5") (pintype "input"))
      (node (ref "IC22") (pin "10") (pinfunction "IN+_10") (pintype "input"))
      (node (ref "IC22") (pin "12") (pinfunction "IN+_12") (pintype "input"))
      (node (ref "IC22") (pin "3") (pinfunction "IN+_3") (pintype "input"))
      (node (ref "IC22") (pin "5") (pinfunction "IN+_5") (pintype "input"))
      (node (ref "IC23") (pin "10") (pinfunction "IN+_10") (pintype "input"))
      (node (ref "IC23") (pin "12") (pinfunction "IN+_12") (pintype "input"))
      (node (ref "IC23") (pin "3") (pinfunction "IN+_3") (pintype "input"))
      (node (ref "IC23") (pin "5") (pinfunction "IN+_5") (pintype "input"))
      (node (ref "IC24") (pin "10") (pinfunction "IN+_10") (pintype "input"))
      (node (ref "IC24") (pin "12") (pinfunction "IN+_12") (pintype "input"))
      (node (ref "IC24") (pin "3") (pinfunction "IN+_3") (pintype "input"))
      (node (ref "IC24") (pin "5") (pinfunction "IN+_5") (pintype "input"))
      (node (ref "IC25") (pin "10") (pinfunction "IN+_10") (pintype "input"))
      (node (ref "IC25") (pin "12") (pinfunction "IN+_12") (pintype "input"))
      (node (ref "IC25") (pin "3") (pinfunction "IN+_3") (pintype "input"))
      (node (ref "IC25") (pin "5") (pinfunction "IN+_5") (pintype "input"))
      (node (ref "IC26") (pin "10") (pinfunction "IN+_10") (pintype "input"))
      (node (ref "IC26") (pin "12") (pinfunction "IN+_12") (pintype "input"))
      (node (ref "IC26") (pin "3") (pinfunction "IN+_3") (pintype "input"))
      (node (ref "IC26") (pin "5") (pinfunction "IN+_5") (pintype "input"))
      (node (ref "IC27") (pin "10") (pinfunction "IN+_10") (pintype "input"))
      (node (ref "IC27") (pin "12") (pinfunction "IN+_12") (pintype "input"))
      (node (ref "IC27") (pin "3") (pinfunction "IN+_3") (pintype "input"))
      (node (ref "IC27") (pin "5") (pinfunction "IN+_5") (pintype "input"))
      (node (ref "JP7") (pin "4") (pinfunction "4_4") (pintype "passive"))
    )
    (net (code "71") (name "/VOUT") (class "Default")
      (node (ref "JP7") (pin "1") (pinfunction "1_1") (pintype "passive"))
      (node (ref "U$3") (pin "28") (pinfunction "D_28") (pintype "bidirectional"))
    )
    (net (code "72") (name "Net-(IC19A-OUT)") (class "Default")
      (node (ref "IC19") (pin "1") (pinfunction "OUT_1") (pintype "output"))
      (node (ref "R1") (pin "1") (pinfunction "1_1") (pintype "passive"))
      (node (ref "R2") (pin "2") (pinfunction "2_2") (pintype "passive"))
    )
    (net (code "73") (name "Net-(IC19B-OUT)") (class "Default")
      (node (ref "IC19") (pin "7") (pinfunction "OUT_7") (pintype "output"))
      (node (ref "R73") (pin "2") (pinfunction "2_2") (pintype "passive"))
      (node (ref "R74") (pin "1") (pinfunction "1_1") (pintype "passive"))
    )
    (net (code "74") (name "Net-(IC19C-IN-)") (class "Default")
      (node (ref "IC19") (pin "9") (pinfunction "IN-_9") (pintype "input"))
      (node (ref "R74") (pin "2") (pinfunction "2_2") (pintype "passive"))
      (node (ref "R75") (pin "1") (pinfunction "1_1") (pintype "passive"))
    )
    (net (code "75") (name "Net-(IC19D-IN-)") (class "Default")
      (node (ref "IC19") (pin "13") (pinfunction "IN-_13") (pintype "input"))
      (node (ref "R1") (pin "2") (pinfunction "2_2") (pintype "passive"))
      (node (ref "R51") (pin "1") (pinfunction "1_1") (pintype "passive"))
    )
    (net (code "76") (name "Net-(IC21A-OUT)") (class "Default")
      (node (ref "IC21") (pin "1") (pinfunction "OUT_1") (pintype "output"))
      (node (ref "R52") (pin "2") (pinfunction "2_2") (pintype "passive"))
      (node (ref "R53") (pin "1") (pinfunction "1_1") (pintype "passive"))
    )
    (net (code "77") (name "Net-(IC21B-OUT)") (class "Default")
      (node (ref "IC21") (pin "7") (pinfunction "OUT_7") (pintype "output"))
      (node (ref "R76") (pin "2") (pinfunction "2_2") (pintype "passive"))
      (node (ref "R77") (pin "1") (pinfunction "1_1") (pintype "passive"))
    )
    (net (code "78") (name "Net-(IC21C-IN-)") (class "Default")
      (node (ref "IC21") (pin "9") (pinfunction "IN-_9") (pintype "input"))
      (node (ref "R77") (pin "2") (pinfunction "2_2") (pintype "passive"))
      (node (ref "R78") (pin "1") (pinfunction "1_1") (pintype "passive"))
    )
    (net (code "79") (name "Net-(IC21D-IN-)") (class "Default")
      (node (ref "IC21") (pin "13") (pinfunction "IN-_13") (pintype "input"))
      (node (ref "R53") (pin "2") (pinfunction "2_2") (pintype "passive"))
      (node (ref "R54") (pin "1") (pinfunction "1_1") (pintype "passive"))
    )
    (net (code "80") (name "Net-(IC22A-OUT)") (class "Default")
      (node (ref "IC22") (pin "1") (pinfunction "OUT_1") (pintype "output"))
      (node (ref "R55") (pin "2") (pinfunction "2_2") (pintype "passive"))
      (node (ref "R56") (pin "1") (pinfunction "1_1") (pintype "passive"))
    )
    (net (code "81") (name "Net-(IC22B-OUT)") (class "Default")
      (node (ref "IC22") (pin "7") (pinfunction "OUT_7") (pintype "output"))
      (node (ref "R79") (pin "2") (pinfunction "2_2") (pintype "passive"))
      (node (ref "R80") (pin "1") (pinfunction "1_1") (pintype "passive"))
    )
    (net (code "82") (name "Net-(IC22C-IN-)") (class "Default")
      (node (ref "IC22") (pin "9") (pinfunction "IN-_9") (pintype "input"))
      (node (ref "R80") (pin "2") (pinfunction "2_2") (pintype "passive"))
      (node (ref "R81") (pin "1") (pinfunction "1_1") (pintype "passive"))
    )
    (net (code "83") (name "Net-(IC22D-IN-)") (class "Default")
      (node (ref "IC22") (pin "13") (pinfunction "IN-_13") (pintype "input"))
      (node (ref "R56") (pin "2") (pinfunction "2_2") (pintype "passive"))
      (node (ref "R57") (pin "1") (pinfunction "1_1") (pintype "passive"))
    )
    (net (code "84") (name "Net-(IC23A-OUT)") (class "Default")
      (node (ref "IC23") (pin "1") (pinfunction "OUT_1") (pintype "output"))
      (node (ref "R58") (pin "2") (pinfunction "2_2") (pintype "passive"))
      (node (ref "R59") (pin "1") (pinfunction "1_1") (pintype "passive"))
    )
    (net (code "85") (name "Net-(IC23B-OUT)") (class "Default")
      (node (ref "IC23") (pin "7") (pinfunction "OUT_7") (pintype "output"))
      (node (ref "R82") (pin "2") (pinfunction "2_2") (pintype "passive"))
      (node (ref "R83") (pin "1") (pinfunction "1_1") (pintype "passive"))
    )
    (net (code "86") (name "Net-(IC23C-IN-)") (class "Default")
      (node (ref "IC23") (pin "9") (pinfunction "IN-_9") (pintype "input"))
      (node (ref "R83") (pin "2") (pinfunction "2_2") (pintype "passive"))
      (node (ref "R84") (pin "1") (pinfunction "1_1") (pintype "passive"))
    )
    (net (code "87") (name "Net-(IC23D-IN-)") (class "Default")
      (node (ref "IC23") (pin "13") (pinfunction "IN-_13") (pintype "input"))
      (node (ref "R59") (pin "2") (pinfunction "2_2") (pintype "passive"))
      (node (ref "R60") (pin "1") (pinfunction "1_1") (pintype "passive"))
    )
    (net (code "88") (name "Net-(IC24A-OUT)") (class "Default")
      (node (ref "IC24") (pin "1") (pinfunction "OUT_1") (pintype "output"))
      (node (ref "R61") (pin "2") (pinfunction "2_2") (pintype "passive"))
      (node (ref "R62") (pin "1") (pinfunction "1_1") (pintype "passive"))
    )
    (net (code "89") (name "Net-(IC24B-OUT)") (class "Default")
      (node (ref "IC24") (pin "7") (pinfunction "OUT_7") (pintype "output"))
      (node (ref "R85") (pin "2") (pinfunction "2_2") (pintype "passive"))
      (node (ref "R86") (pin "1") (pinfunction "1_1") (pintype "passive"))
    )
    (net (code "90") (name "Net-(IC24C-IN-)") (class "Default")
      (node (ref "IC24") (pin "9") (pinfunction "IN-_9") (pintype "input"))
      (node (ref "R86") (pin "2") (pinfunction "2_2") (pintype "passive"))
      (node (ref "R87") (pin "1") (pinfunction "1_1") (pintype "passive"))
    )
    (net (code "91") (name "Net-(IC24D-IN-)") (class "Default")
      (node (ref "IC24") (pin "13") (pinfunction "IN-_13") (pintype "input"))
      (node (ref "R62") (pin "2") (pinfunction "2_2") (pintype "passive"))
      (node (ref "R63") (pin "1") (pinfunction "1_1") (pintype "passive"))
    )
    (net (code "92") (name "Net-(IC25A-OUT)") (class "Default")
      (node (ref "IC25") (pin "1") (pinfunction "OUT_1") (pintype "output"))
      (node (ref "R64") (pin "2") (pinfunction "2_2") (pintype "passive"))
      (node (ref "R65") (pin "1") (pinfunction "1_1") (pintype "passive"))
    )
    (net (code "93") (name "Net-(IC25B-OUT)") (class "Default")
      (node (ref "IC25") (pin "7") (pinfunction "OUT_7") (pintype "output"))
      (node (ref "R88") (pin "2") (pinfunction "2_2") (pintype "passive"))
      (node (ref "R89") (pin "1") (pinfunction "1_1") (pintype "passive"))
    )
    (net (code "94") (name "Net-(IC25C-IN-)") (class "Default")
      (node (ref "IC25") (pin "9") (pinfunction "IN-_9") (pintype "input"))
      (node (ref "R89") (pin "2") (pinfunction "2_2") (pintype "passive"))
      (node (ref "R90") (pin "1") (pinfunction "1_1") (pintype "passive"))
    )
    (net (code "95") (name "Net-(IC25D-IN-)") (class "Default")
      (node (ref "IC25") (pin "13") (pinfunction "IN-_13") (pintype "input"))
      (node (ref "R65") (pin "2") (pinfunction "2_2") (pintype "passive"))
      (node (ref "R66") (pin "1") (pinfunction "1_1") (pintype "passive"))
    )
    (net (code "96") (name "Net-(IC26A-OUT)") (class "Default")
      (node (ref "IC26") (pin "1") (pinfunction "OUT_1") (pintype "output"))
      (node (ref "R67") (pin "2") (pinfunction "2_2") (pintype "passive"))
      (node (ref "R68") (pin "1") (pinfunction "1_1") (pintype "passive"))
    )
    (net (code "97") (name "Net-(IC26B-OUT)") (class "Default")
      (node (ref "IC26") (pin "7") (pinfunction "OUT_7") (pintype "output"))
      (node (ref "R91") (pin "2") (pinfunction "2_2") (pintype "passive"))
      (node (ref "R92") (pin "1") (pinfunction "1_1") (pintype "passive"))
    )
    (net (code "98") (name "Net-(IC26C-IN-)") (class "Default")
      (node (ref "IC26") (pin "9") (pinfunction "IN-_9") (pintype "input"))
      (node (ref "R92") (pin "2") (pinfunction "2_2") (pintype "passive"))
      (node (ref "R93") (pin "1") (pinfunction "1_1") (pintype "passive"))
    )
    (net (code "99") (name "Net-(IC26D-IN-)") (class "Default")
      (node (ref "IC26") (pin "13") (pinfunction "IN-_13") (pintype "input"))
      (node (ref "R68") (pin "2") (pinfunction "2_2") (pintype "passive"))
      (node (ref "R69") (pin "1") (pinfunction "1_1") (pintype "passive"))
    )
    (net (code "100") (name "Net-(IC27A-OUT)") (class "Default")
      (node (ref "IC27") (pin "1") (pinfunction "OUT_1") (pintype "output"))
      (node (ref "R70") (pin "2") (pinfunction "2_2") (pintype "passive"))
      (node (ref "R71") (pin "1") (pinfunction "1_1") (pintype "passive"))
    )
    (net (code "101") (name "Net-(IC27B-OUT)") (class "Default")
      (node (ref "IC27") (pin "7") (pinfunction "OUT_7") (pintype "output"))
      (node (ref "R94") (pin "2") (pinfunction "2_2") (pintype "passive"))
      (node (ref "R95") (pin "1") (pinfunction "1_1") (pintype "passive"))
    )
    (net (code "102") (name "Net-(IC27C-IN-)") (class "Default")
      (node (ref "IC27") (pin "9") (pinfunction "IN-_9") (pintype "input"))
      (node (ref "R95") (pin "2") (pinfunction "2_2") (pintype "passive"))
      (node (ref "R96") (pin "1") (pinfunction "1_1") (pintype "passive"))
    )
    (net (code "103") (name "Net-(IC27D-IN-)") (class "Default")
      (node (ref "IC27") (pin "13") (pinfunction "IN-_13") (pintype "input"))
      (node (ref "R71") (pin "2") (pinfunction "2_2") (pintype "passive"))
      (node (ref "R72") (pin "1") (pinfunction "1_1") (pintype "passive"))
    )
    (net (code "104") (name "unconnected-(JP5-Pad3)") (class "Default")
      (node (ref "JP5") (pin "3") (pinfunction "3_3") (pintype "passive"))
    )
    (net (code "105") (name "unconnected-(JP5-Pad4)") (class "Default")
      (node (ref "JP5") (pin "4") (pinfunction "4_4") (pintype "passive"))
    )
    (net (code "106") (name "unconnected-(JP11-Pad4)") (class "Default")
      (node (ref "JP11") (pin "4") (pinfunction "4_4") (pintype "passive"))
    )
    (net (code "107") (name "unconnected-(JP12-Pad1)") (class "Default")
      (node (ref "JP12") (pin "1") (pinfunction "1_1") (pintype "passive"))
    )
    (net (code "108") (name "unconnected-(JP12-Pad2)") (class "Default")
      (node (ref "JP12") (pin "2") (pinfunction "2_2") (pintype "passive"))
    )
    (net (code "109") (name "unconnected-(JP12-Pad3)") (class "Default")
      (node (ref "JP12") (pin "3") (pinfunction "3_3") (pintype "passive"))
    )
    (net (code "110") (name "unconnected-(JP12-Pad4)") (class "Default")
      (node (ref "JP12") (pin "4") (pinfunction "4_4") (pintype "passive"))
    )
    (net (code "111") (name "unconnected-(JP13-Pad1)") (class "Default")
      (node (ref "JP13") (pin "1") (pinfunction "1_1") (pintype "passive"))
    )
    (net (code "112") (name "unconnected-(JP13-Pad2)") (class "Default")
      (node (ref "JP13") (pin "2") (pinfunction "2_2") (pintype "passive"))
    )
    (net (code "113") (name "unconnected-(JP13-Pad3)") (class "Default")
      (node (ref "JP13") (pin "3") (pinfunction "3_3") (pintype "passive"))
    )
    (net (code "114") (name "unconnected-(JP13-Pad4)") (class "Default")
      (node (ref "JP13") (pin "4") (pinfunction "4_4") (pintype "passive"))
    )
    (net (code "115") (name "unconnected-(JP14-Pad9)") (class "Default")
      (node (ref "JP14") (pin "9") (pinfunction "9_9") (pintype "passive"))
    )
    (net (code "116") (name "unconnected-(JP14-Pad10)") (class "Default")
      (node (ref "JP14") (pin "10") (pinfunction "10_10") (pintype "passive"))
    )
  )
)
